# logmega082.net
KiCad netlist of a schematic drawn in EAGLE
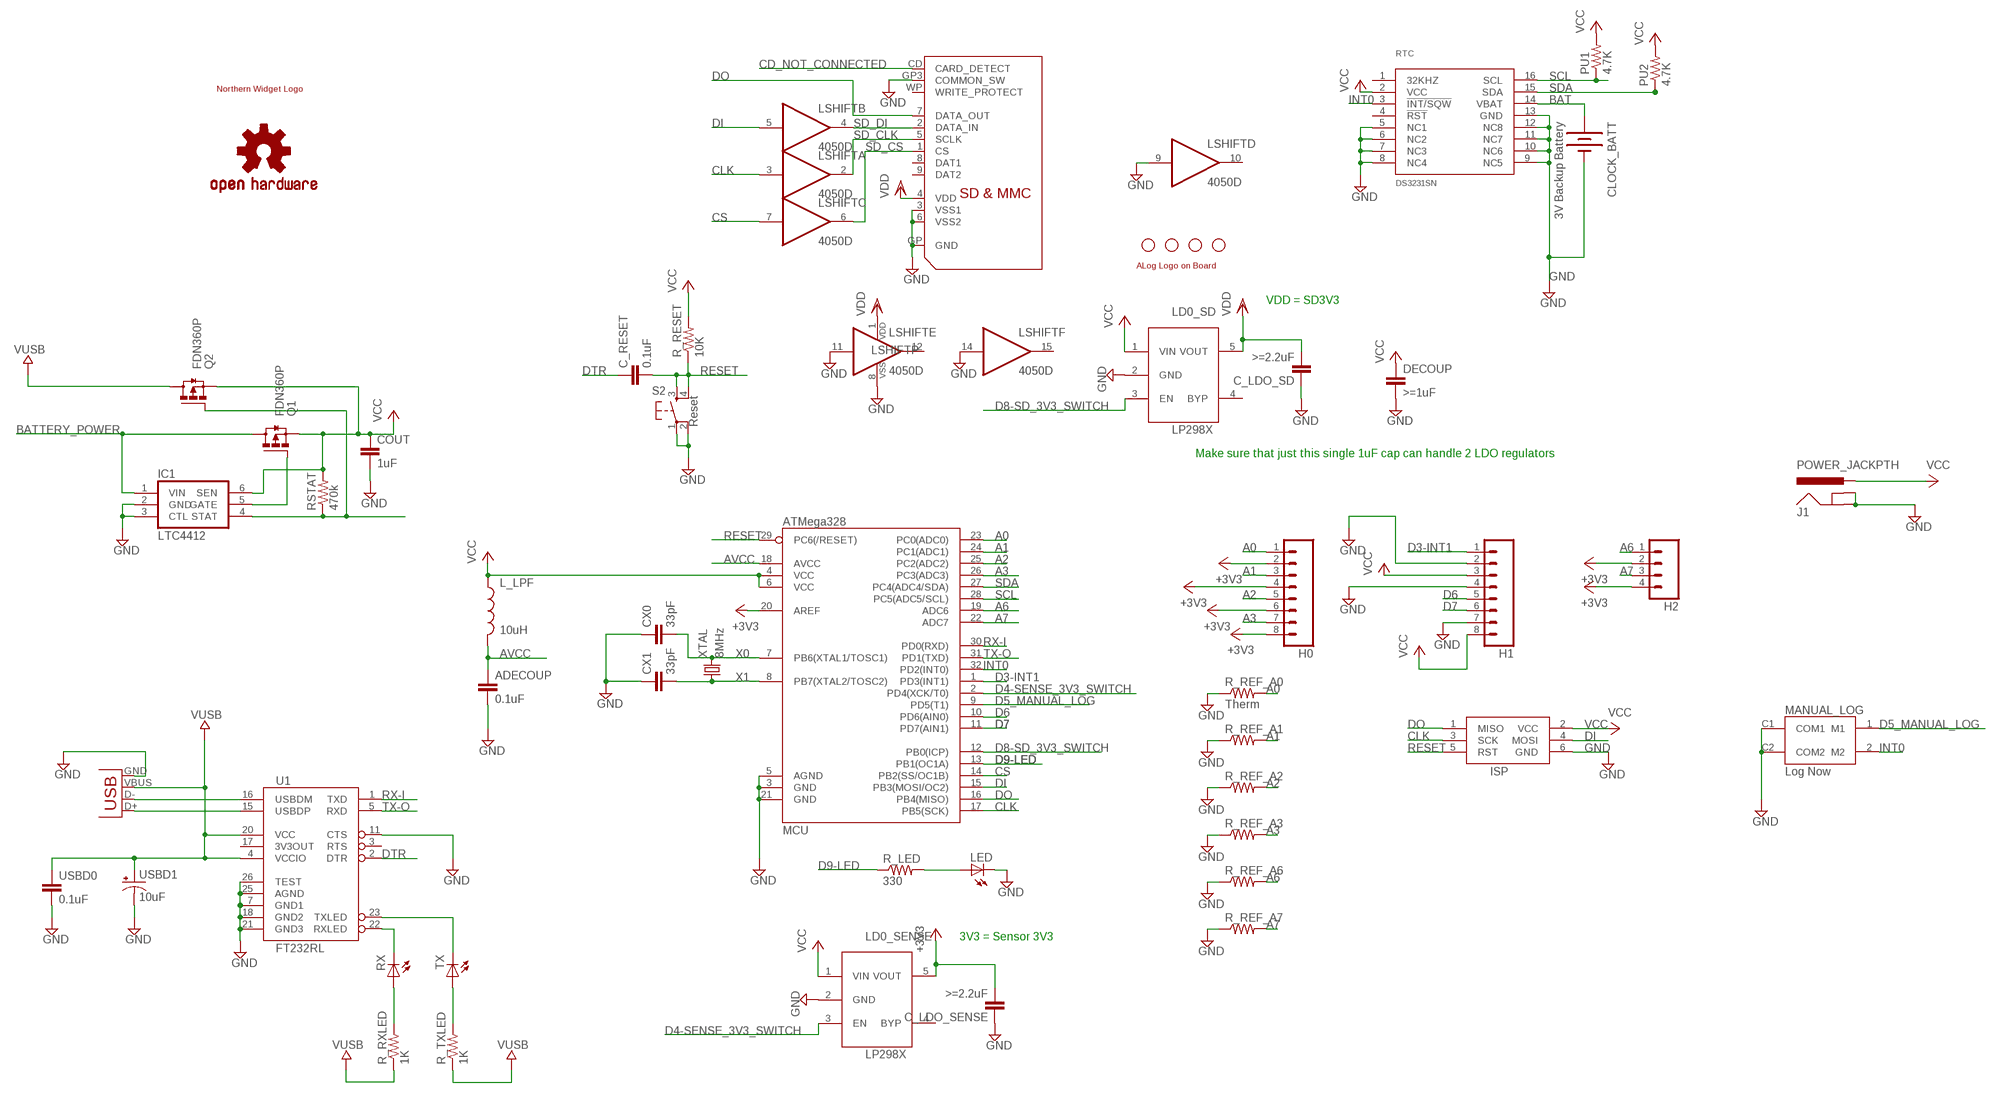
[diagram p0: schematic, sheet 1, part 1 of 2]
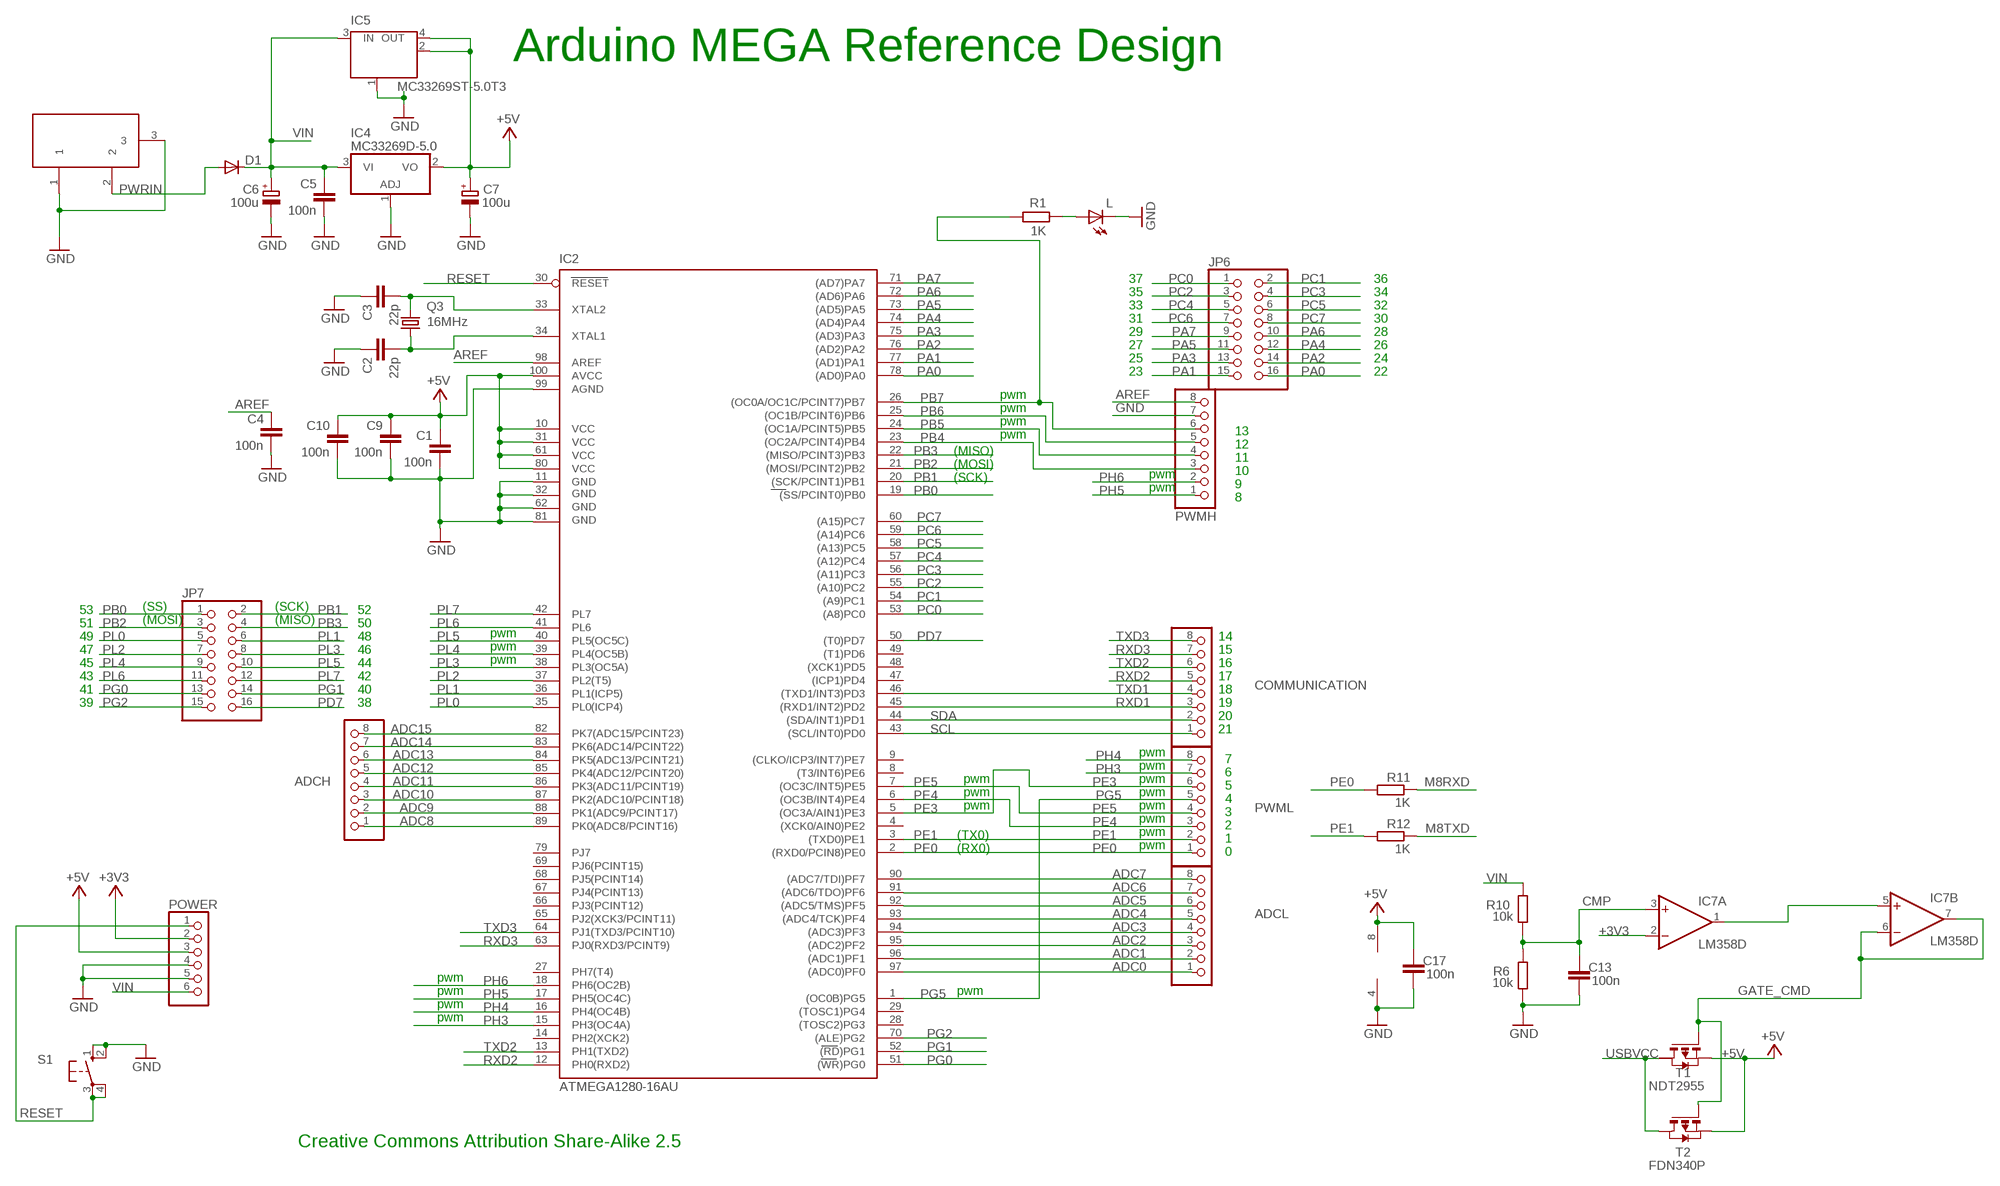
[diagram p1: schematic, sheet 1, part 2 of 2]

(export (version "E")
  (design (tool "Eeschema 10.0.6"))
  (components
    (comp (ref "ADCH")
      (value "PINHD-1X8")
      (footprint "eagle-import:1X08")
      (libsource (lib "eagle-import") (part "PINHD-1X8"))
    )
    (comp (ref "ADCL")
      (value "PINHD-1X8")
      (footprint "eagle-import:1X08")
      (libsource (lib "eagle-import") (part "PINHD-1X8"))
    )
    (comp (ref "ADECOUP")
      (value "0.1uF")
      (footprint "eagle-import:C0603")
      (libsource (lib "eagle-import") (part "resistor_C-EUC0603"))
    )
    (comp (ref "C1")
      (value "100n")
      (footprint "eagle-import:C0805RND")
      (libsource (lib "eagle-import") (part "rcl_C-EU"))
    )
    (comp (ref "C2")
      (value "22p")
      (footprint "eagle-import:C0805RND")
      (libsource (lib "eagle-import") (part "rcl_C-EU"))
    )
    (comp (ref "C3")
      (value "22p")
      (footprint "eagle-import:C0805RND")
      (libsource (lib "eagle-import") (part "rcl_C-EU"))
    )
    (comp (ref "C4")
      (value "100n")
      (footprint "eagle-import:C0805RND")
      (libsource (lib "eagle-import") (part "rcl_C-EU"))
    )
    (comp (ref "C5")
      (value "100n")
      (footprint "eagle-import:C0805RND")
      (libsource (lib "eagle-import") (part "rcl_C-EU"))
    )
    (comp (ref "C6")
      (value "100u")
      (footprint "eagle-import:SMC_D")
      (libsource (lib "eagle-import") (part "CPOL-EUSMCD"))
    )
    (comp (ref "C7")
      (value "100u")
      (footprint "eagle-import:SMC_D")
      (libsource (lib "eagle-import") (part "CPOL-EUSMCD"))
    )
    (comp (ref "C9")
      (value "100n")
      (footprint "eagle-import:C0805RND")
      (libsource (lib "eagle-import") (part "rcl_C-EU"))
    )
    (comp (ref "C10")
      (value "100n")
      (footprint "eagle-import:C0805RND")
      (libsource (lib "eagle-import") (part "rcl_C-EU"))
    )
    (comp (ref "C13")
      (value "100n")
      (footprint "eagle-import:C0805RND")
      (libsource (lib "eagle-import") (part "rcl_C-EU"))
    )
    (comp (ref "C17")
      (value "100n")
      (footprint "eagle-import:C0805RND")
      (libsource (lib "eagle-import") (part "rcl_C-EU"))
    )
    (comp (ref "CLOCK_BATT")
      (value "3V Backup Battery")
      (footprint "eagle-import:BATTCON_12MM_PTH")
      (libsource (lib "eagle-import") (part "BATTERY12PTH"))
    )
    (comp (ref "COMMUNICATION")
      (value "PINHD-1X8")
      (footprint "eagle-import:1X08")
      (libsource (lib "eagle-import") (part "PINHD-1X8"))
    )
    (comp (ref "COUT")
      (value "1uF")
      (footprint "eagle-import:C0603-ROUND")
      (libsource (lib "eagle-import") (part "C-EUC0603"))
    )
    (comp (ref "CX0")
      (value "33pF")
      (footprint "eagle-import:C0603")
      (libsource (lib "eagle-import") (part "resistor_C-EUC0603"))
    )
    (comp (ref "CX1")
      (value "33pF")
      (footprint "eagle-import:C0603")
      (libsource (lib "eagle-import") (part "resistor_C-EUC0603"))
    )
    (comp (ref "C_LDO_SD")
      (value ">=2.2uF")
      (footprint "eagle-import:C0603")
      (libsource (lib "eagle-import") (part "resistor_C-EUC0603"))
    )
    (comp (ref "C_LDO_SENSE")
      (value ">=2.2uF")
      (footprint "eagle-import:C0603")
      (libsource (lib "eagle-import") (part "resistor_C-EUC0603"))
    )
    (comp (ref "C_RESET")
      (value "0.1uF")
      (footprint "eagle-import:C0603")
      (libsource (lib "eagle-import") (part "resistor_C-EUC0603"))
    )
    (comp (ref "D1")
      (value "DIODE-SMB")
      (footprint "eagle-import:SMB")
      (libsource (lib "eagle-import") (part "DIODE-SMB"))
    )
    (comp (ref "DECOUP")
      (value ">=1uF")
      (footprint "eagle-import:C0603")
      (libsource (lib "eagle-import") (part "resistor_C-EUC0603"))
    )
    (comp (ref "H0")
      (value "M083.5MM-8")
      (footprint "eagle-import:SCREWTERMINAL-3.5MM-8")
      (libsource (lib "eagle-import") (part "M083.5MM-8"))
    )
    (comp (ref "H1")
      (value "M083.5MM-8")
      (footprint "eagle-import:SCREWTERMINAL-3.5MM-8")
      (libsource (lib "eagle-import") (part "M083.5MM-8"))
    )
    (comp (ref "H2")
      (value "M04SCREW")
      (footprint "eagle-import:SCREWTERMINAL-3.5MM-4")
      (libsource (lib "eagle-import") (part "M04SCREW"))
    )
    (comp (ref "IC1")
      (value "LTC4412")
      (footprint "eagle-import:TSOT23-6")
      (libsource (lib "eagle-import") (part "LTC4412S6E"))
    )
    (comp (ref "IC2")
      (value "ATMEGA1280-16AU")
      (footprint "eagle-import:TQFP100")
      (libsource (lib "eagle-import") (part "ATMEGAAU1280-16"))
    )
    (comp (ref "IC4")
      (value "MC33269D-5.0")
      (footprint "eagle-import:DPACK")
      (libsource (lib "eagle-import") (part "MC33269?D-5.0"))
    )
    (comp (ref "IC5")
      (value "MC33269ST-5.0T3")
      (footprint "eagle-import:SOT223")
      (libsource (lib "eagle-import") (part "MC33269ST-3.3T3"))
    )
    (comp (ref "IC7")
      (value "LM358D")
      (footprint "eagle-import:SO08")
      (libsource (lib "eagle-import") (part "LM358D"))
    )
    (comp (ref "ISP")
      (value "AVRISP-6")
      (footprint "eagle-import:AVRISP")
      (libsource (lib "eagle-import") (part "AVRISP-6"))
    )
    (comp (ref "J1")
      (value "POWER_JACKPTH")
      (footprint "eagle-import:POWER_JACK_PTH")
      (libsource (lib "eagle-import") (part "POWER_JACKPTH"))
    )
    (comp (ref "JP1")
      (value "STAND-OFF")
      (footprint "eagle-import:STAND-OFF")
      (libsource (lib "eagle-import") (part "STAND-OFF"))
    )
    (comp (ref "JP2")
      (value "STAND-OFF")
      (footprint "eagle-import:STAND-OFF")
      (libsource (lib "eagle-import") (part "STAND-OFF"))
    )
    (comp (ref "JP3")
      (value "STAND-OFF")
      (footprint "eagle-import:STAND-OFF")
      (libsource (lib "eagle-import") (part "STAND-OFF"))
    )
    (comp (ref "JP4")
      (value "STAND-OFF")
      (footprint "eagle-import:STAND-OFF")
      (libsource (lib "eagle-import") (part "STAND-OFF"))
    )
    (comp (ref "JP5")
      (value "USB-B")
      (footprint "eagle-import:USB-B-PTH")
      (libsource (lib "eagle-import") (part "USBPTH"))
    )
    (comp (ref "JP6")
      (value "PINHD-2X8")
      (footprint "eagle-import:2X08")
      (libsource (lib "eagle-import") (part "PINHD-2X8"))
    )
    (comp (ref "JP7")
      (value "PINHD-2X8")
      (footprint "eagle-import:2X08")
      (libsource (lib "eagle-import") (part "PINHD-2X8"))
    )
    (comp (ref "L")
      (value "LED0805ROUND")
      (footprint "eagle-import:0805RND")
      (libsource (lib "eagle-import") (part "LED0805ROUND"))
    )
    (comp (ref "LD0_SD")
      (value "LP2985")
      (footprint "eagle-import:SOT23-5L")
      (libsource (lib "eagle-import") (part "LP298XS"))
    )
    (comp (ref "LD0_SENSE")
      (value "LP2985")
      (footprint "eagle-import:SOT23-5L")
      (libsource (lib "eagle-import") (part "LP298XS"))
    )
    (comp (ref "LED")
      (value "LED3MM")
      (footprint "eagle-import:LED3MM")
      (libsource (lib "eagle-import") (part "LED3MM"))
    )
    (comp (ref "LOGO1")
      (value "OSHW-LOGOM")
      (footprint "eagle-import:OSHW-LOGO-M")
      (libsource (lib "eagle-import") (part "OSHW-LOGOM"))
    )
    (comp (ref "LSHIFT")
      (value "4050D")
      (footprint "eagle-import:SO16")
      (libsource (lib "eagle-import") (part "4050D"))
    )
    (comp (ref "L_LPF")
      (value "10uH")
      (footprint "eagle-import:0805")
      (libsource (lib "eagle-import") (part "INDUCTOR0805"))
    )
    (comp (ref "MANUAL_LOG")
      (value "Log Now")
      (footprint "eagle-import:TL_BUTTON")
      (libsource (lib "eagle-import") (part "TL3350'TL3350'"))
    )
    (comp (ref "MCU")
      (value "ATMega328")
      (footprint "eagle-import:TQFP32-08")
      (libsource (lib "eagle-import") (part "ATMEGA168"))
    )
    (comp (ref "POWER")
      (value "PINHD-1X6")
      (footprint "eagle-import:1X06")
      (libsource (lib "eagle-import") (part "PINHD-1X6"))
    )
    (comp (ref "PU1")
      (value "4.7K")
      (footprint "eagle-import:R0603@1")
      (libsource (lib "eagle-import") (part "R-US_R0603"))
    )
    (comp (ref "PU2")
      (value "4.7K")
      (footprint "eagle-import:R0603@1")
      (libsource (lib "eagle-import") (part "R-US_R0603"))
    )
    (comp (ref "PWMH")
      (value "PINHD-1X8")
      (footprint "eagle-import:1X08")
      (libsource (lib "eagle-import") (part "PINHD-1X8"))
    )
    (comp (ref "PWML")
      (value "PINHD-1X8")
      (footprint "eagle-import:1X08")
      (libsource (lib "eagle-import") (part "PINHD-1X8"))
    )
    (comp (ref "Q1")
      (value "FDN360P")
      (footprint "eagle-import:SUPER-SOT3")
      (libsource (lib "eagle-import") (part "FDN360P"))
    )
    (comp (ref "Q2")
      (value "FDN360P")
      (footprint "eagle-import:SUPER-SOT3")
      (libsource (lib "eagle-import") (part "FDN360P"))
    )
    (comp (ref "Q3")
      (value "16MHz")
      (footprint "eagle-import:HC49_S")
      (libsource (lib "eagle-import") (part "CRYTALHC49S"))
    )
    (comp (ref "R1")
      (value "1K")
      (footprint "eagle-import:R0805RND")
      (libsource (lib "eagle-import") (part "rcl_R-EU_"))
    )
    (comp (ref "R6")
      (value "10k")
      (footprint "eagle-import:R0805RND")
      (libsource (lib "eagle-import") (part "rcl_R-EU_"))
    )
    (comp (ref "R10")
      (value "10k")
      (footprint "eagle-import:R0805RND")
      (libsource (lib "eagle-import") (part "rcl_R-EU_"))
    )
    (comp (ref "R11")
      (value "1K")
      (footprint "eagle-import:RCL_0805RND")
      (libsource (lib "eagle-import") (part "R-EU_"))
    )
    (comp (ref "R12")
      (value "1K")
      (footprint "eagle-import:RCL_0805RND")
      (libsource (lib "eagle-import") (part "R-EU_"))
    )
    (comp (ref "RSTAT")
      (value "470k")
      (footprint "eagle-import:R0603@1")
      (libsource (lib "eagle-import") (part "R-US_R0603"))
    )
    (comp (ref "RTC")
      (value "DS3231SN")
      (footprint "eagle-import:SO16W")
      (libsource (lib "eagle-import") (part "DS3231SN"))
    )
    (comp (ref "RX")
      (value "LED0603")
      (footprint "eagle-import:LED-0603")
      (libsource (lib "eagle-import") (part "SparkFun-LED_LED0603"))
    )
    (comp (ref "R_LED")
      (value "330")
      (footprint "eagle-import:R0603@1")
      (libsource (lib "eagle-import") (part "R-US_R0603"))
    )
    (comp (ref "R_REF_A0")
      (value "Therm")
      (footprint "eagle-import:0207_10")
      (libsource (lib "eagle-import") (part "resistor_R-US_0207/10"))
    )
    (comp (ref "R_REF_A1")
      (value "R-US_0207/10")
      (footprint "eagle-import:0207_10")
      (libsource (lib "eagle-import") (part "resistor_R-US_0207/10"))
    )
    (comp (ref "R_REF_A2")
      (value "R-US_0207/10")
      (footprint "eagle-import:0207_10")
      (libsource (lib "eagle-import") (part "resistor_R-US_0207/10"))
    )
    (comp (ref "R_REF_A3")
      (value "R-US_0207/10")
      (footprint "eagle-import:0207_10")
      (libsource (lib "eagle-import") (part "resistor_R-US_0207/10"))
    )
    (comp (ref "R_REF_A6")
      (value "R-US_0207/10")
      (footprint "eagle-import:0207_10")
      (libsource (lib "eagle-import") (part "resistor_R-US_0207/10"))
    )
    (comp (ref "R_REF_A7")
      (value "R-US_0207/10")
      (footprint "eagle-import:0207_10")
      (libsource (lib "eagle-import") (part "resistor_R-US_0207/10"))
    )
    (comp (ref "R_RESET")
      (value "10K")
      (footprint "eagle-import:R0603@1")
      (libsource (lib "eagle-import") (part "R-US_R0603"))
    )
    (comp (ref "R_RXLED")
      (value "1K")
      (footprint "eagle-import:R0603@1")
      (libsource (lib "eagle-import") (part "R-US_R0603"))
    )
    (comp (ref "R_TXLED")
      (value "1K")
      (footprint "eagle-import:R0603@1")
      (libsource (lib "eagle-import") (part "R-US_R0603"))
    )
    (comp (ref "S1")
      (value "10-XX")
      (footprint "eagle-import:B3F-10XX")
      (libsource (lib "eagle-import") (part "10-XX"))
    )
    (comp (ref "S2")
      (value "Reset")
      (footprint "eagle-import:TACTILE_SWITCH_SMD")
      (libsource (lib "eagle-import") (part "TAC_SWITCHSND"))
    )
    (comp (ref "SD")
      (value "SDMMC06132")
      (footprint "eagle-import:06132")
      (libsource (lib "eagle-import") (part "SDMMC06132"))
    )
    (comp (ref "T1")
      (value "NDT2955")
      (footprint "eagle-import:SOT223")
      (libsource (lib "eagle-import") (part "PMOSSOT223"))
    )
    (comp (ref "T2")
      (value "FDN340P")
      (footprint "eagle-import:SOT-23")
      (libsource (lib "eagle-import") (part "PMOSSOT23"))
    )
    (comp (ref "TX")
      (value "LED0603")
      (footprint "eagle-import:LED-0603")
      (libsource (lib "eagle-import") (part "SparkFun-LED_LED0603"))
    )
    (comp (ref "U$1")
      (value "NWLOGO")
      (footprint "eagle-import:NWLOGO")
      (libsource (lib "eagle-import") (part "NWLOGO"))
    )
    (comp (ref "U$2")
      (value "ALOG_LOGO_V1_5.5MM")
      (footprint "eagle-import:ALOG_LOGO_V1_SMALL")
      (libsource (lib "eagle-import") (part "ALOG_LOGO_V1_5.5MM"))
    )
    (comp (ref "U1")
      (value "FT232RL")
      (footprint "eagle-import:SSOP28DB")
      (libsource (lib "eagle-import") (part "FT232RL-BASICSSOP"))
    )
    (comp (ref "USBD0")
      (value "0.1uF")
      (footprint "eagle-import:C0603")
      (libsource (lib "eagle-import") (part "resistor_C-EUC0603"))
    )
    (comp (ref "USBD1")
      (value "10uF")
      (footprint "eagle-import:EIA3216")
      (libsource (lib "eagle-import") (part "CAP_POL1206"))
    )
    (comp (ref "X2")
      (value "DC21MMX")
      (footprint "eagle-import:DC-21MM")
      (libsource (lib "eagle-import") (part "DC21MMX"))
    )
    (comp (ref "XTAL")
      (value "8MHz")
      (footprint "eagle-import:HC49U-V")
      (libsource (lib "eagle-import") (part "CRYSTALHC49UV"))
    )
  )
  (nets
    (net (code "1") (name "+3V3") (class "Default")
      (node (ref "C_LDO_SENSE") (pin "2") (pinfunction "2_2") (pintype "passive"))
      (node (ref "H0") (pin "2") (pinfunction "2_2") (pintype "passive"))
      (node (ref "H0") (pin "4") (pinfunction "4_4") (pintype "passive"))
      (node (ref "H0") (pin "6") (pinfunction "6_6") (pintype "passive"))
      (node (ref "H0") (pin "8") (pinfunction "8_8") (pintype "passive"))
      (node (ref "H2") (pin "2") (pinfunction "2_2") (pintype "passive"))
      (node (ref "H2") (pin "4") (pinfunction "4_4") (pintype "passive"))
      (node (ref "IC7") (pin "2") (pinfunction "-IN_2") (pintype "input"))
      (node (ref "LD0_SENSE") (pin "5") (pinfunction "VOUT_5") (pintype "bidirectional"))
      (node (ref "MCU") (pin "20") (pinfunction "AREF_20") (pintype "bidirectional"))
      (node (ref "POWER") (pin "2") (pinfunction "2_2") (pintype "passive"))
    )
    (net (code "2") (name "+5V") (class "Default")
      (node (ref "C1") (pin "1") (pinfunction "1_1") (pintype "passive"))
      (node (ref "C10") (pin "1") (pinfunction "1_1") (pintype "passive"))
      (node (ref "C17") (pin "2") (pinfunction "2_2") (pintype "passive"))
      (node (ref "C7") (pin "+") (pinfunction "+_+") (pintype "passive"))
      (node (ref "C9") (pin "1") (pinfunction "1_1") (pintype "passive"))
      (node (ref "IC2") (pin "10") (pinfunction "VCC_10") (pintype "power_in"))
      (node (ref "IC2") (pin "100") (pinfunction "AVCC_100") (pintype "power_in"))
      (node (ref "IC2") (pin "31") (pinfunction "VCC1_31") (pintype "power_in"))
      (node (ref "IC2") (pin "61") (pinfunction "VCC2_61") (pintype "power_in"))
      (node (ref "IC2") (pin "80") (pinfunction "VCC3_80") (pintype "power_in"))
      (node (ref "IC4") (pin "2") (pinfunction "VO_2") (pintype "passive"))
      (node (ref "IC5") (pin "2") (pinfunction "OUT_2") (pintype "passive"))
      (node (ref "IC5") (pin "4") (pinfunction "OUT_4") (pintype "passive"))
      (node (ref "IC7") (pin "8") (pinfunction "V+_8") (pintype "power_in"))
      (node (ref "POWER") (pin "3") (pinfunction "3_3") (pintype "passive"))
      (node (ref "T1") (pin "3") (pinfunction "S_3") (pintype "passive"))
      (node (ref "T2") (pin "2") (pinfunction "S_2") (pintype "passive"))
    )
    (net (code "3") (name "/A0") (class "Default")
      (node (ref "H0") (pin "1") (pinfunction "1_1") (pintype "passive"))
      (node (ref "MCU") (pin "23") (pinfunction "PC0(ADC0)_23") (pintype "bidirectional"))
      (node (ref "R_REF_A0") (pin "2") (pinfunction "2_2") (pintype "passive"))
    )
    (net (code "4") (name "/A1") (class "Default")
      (node (ref "H0") (pin "3") (pinfunction "3_3") (pintype "passive"))
      (node (ref "MCU") (pin "24") (pinfunction "PC1(ADC1)_24") (pintype "bidirectional"))
      (node (ref "R_REF_A1") (pin "2") (pinfunction "2_2") (pintype "passive"))
    )
    (net (code "5") (name "/A2") (class "Default")
      (node (ref "H0") (pin "5") (pinfunction "5_5") (pintype "passive"))
      (node (ref "MCU") (pin "25") (pinfunction "PC2(ADC2)_25") (pintype "bidirectional"))
      (node (ref "R_REF_A2") (pin "2") (pinfunction "2_2") (pintype "passive"))
    )
    (net (code "6") (name "/A3") (class "Default")
      (node (ref "H0") (pin "7") (pinfunction "7_7") (pintype "passive"))
      (node (ref "MCU") (pin "26") (pinfunction "PC3(ADC3)_26") (pintype "bidirectional"))
      (node (ref "R_REF_A3") (pin "2") (pinfunction "2_2") (pintype "passive"))
    )
    (net (code "7") (name "/A6") (class "Default")
      (node (ref "H2") (pin "1") (pinfunction "1_1") (pintype "passive"))
      (node (ref "MCU") (pin "19") (pinfunction "ADC6_19") (pintype "bidirectional"))
      (node (ref "R_REF_A6") (pin "2") (pinfunction "2_2") (pintype "passive"))
    )
    (net (code "8") (name "/A7") (class "Default")
      (node (ref "H2") (pin "3") (pinfunction "3_3") (pintype "passive"))
      (node (ref "MCU") (pin "22") (pinfunction "ADC7_22") (pintype "bidirectional"))
      (node (ref "R_REF_A7") (pin "2") (pinfunction "2_2") (pintype "passive"))
    )
    (net (code "9") (name "/ADC0") (class "Default")
      (node (ref "ADCL") (pin "1") (pinfunction "1_1") (pintype "passive"))
      (node (ref "IC2") (pin "97") (pinfunction "(ADC0)PF0_97") (pintype "bidirectional"))
    )
    (net (code "10") (name "/ADC1") (class "Default")
      (node (ref "ADCL") (pin "2") (pinfunction "2_2") (pintype "passive"))
      (node (ref "IC2") (pin "96") (pinfunction "(ADC1)PF1_96") (pintype "bidirectional"))
    )
    (net (code "11") (name "/ADC2") (class "Default")
      (node (ref "ADCL") (pin "3") (pinfunction "3_3") (pintype "passive"))
      (node (ref "IC2") (pin "95") (pinfunction "(ADC2)PF2_95") (pintype "bidirectional"))
    )
    (net (code "12") (name "/ADC3") (class "Default")
      (node (ref "ADCL") (pin "4") (pinfunction "4_4") (pintype "passive"))
      (node (ref "IC2") (pin "94") (pinfunction "(ADC3)PF3_94") (pintype "bidirectional"))
    )
    (net (code "13") (name "/ADC4") (class "Default")
      (node (ref "ADCL") (pin "5") (pinfunction "5_5") (pintype "passive"))
      (node (ref "IC2") (pin "93") (pinfunction "(ADC4/TCK)PF4_93") (pintype "bidirectional"))
    )
    (net (code "14") (name "/ADC5") (class "Default")
      (node (ref "ADCL") (pin "6") (pinfunction "6_6") (pintype "passive"))
      (node (ref "IC2") (pin "92") (pinfunction "(ADC5/TMS)PF5_92") (pintype "bidirectional"))
    )
    (net (code "15") (name "/ADC6") (class "Default")
      (node (ref "ADCL") (pin "7") (pinfunction "7_7") (pintype "passive"))
      (node (ref "IC2") (pin "91") (pinfunction "(ADC6/TDO)PF6_91") (pintype "bidirectional"))
    )
    (net (code "16") (name "/ADC7") (class "Default")
      (node (ref "ADCL") (pin "8") (pinfunction "8_8") (pintype "passive"))
      (node (ref "IC2") (pin "90") (pinfunction "(ADC7/TDI)PF7_90") (pintype "bidirectional"))
    )
    (net (code "17") (name "/ADC8") (class "Default")
      (node (ref "ADCH") (pin "1") (pinfunction "1_1") (pintype "passive"))
      (node (ref "IC2") (pin "89") (pinfunction "PK0(ADC8/PCINT16)_89") (pintype "bidirectional"))
    )
    (net (code "18") (name "/ADC9") (class "Default")
      (node (ref "ADCH") (pin "2") (pinfunction "2_2") (pintype "passive"))
      (node (ref "IC2") (pin "88") (pinfunction "PK1(ADC9/PCINT17)_88") (pintype "bidirectional"))
    )
    (net (code "19") (name "/ADC10") (class "Default")
      (node (ref "ADCH") (pin "3") (pinfunction "3_3") (pintype "passive"))
      (node (ref "IC2") (pin "87") (pinfunction "PK2(ADC10/PCINT18)_87") (pintype "bidirectional"))
    )
    (net (code "20") (name "/ADC11") (class "Default")
      (node (ref "ADCH") (pin "4") (pinfunction "4_4") (pintype "passive"))
      (node (ref "IC2") (pin "86") (pinfunction "PK3(ADC11/PCINT19)_86") (pintype "bidirectional"))
    )
    (net (code "21") (name "/ADC12") (class "Default")
      (node (ref "ADCH") (pin "5") (pinfunction "5_5") (pintype "passive"))
      (node (ref "IC2") (pin "85") (pinfunction "PK4(ADC12/PCINT20)_85") (pintype "bidirectional"))
    )
    (net (code "22") (name "/ADC13") (class "Default")
      (node (ref "ADCH") (pin "6") (pinfunction "6_6") (pintype "passive"))
      (node (ref "IC2") (pin "84") (pinfunction "PK5(ADC13/PCINT21)_84") (pintype "bidirectional"))
    )
    (net (code "23") (name "/ADC14") (class "Default")
      (node (ref "ADCH") (pin "7") (pinfunction "7_7") (pintype "passive"))
      (node (ref "IC2") (pin "83") (pinfunction "PK6(ADC14/PCINT22)_83") (pintype "bidirectional"))
    )
    (net (code "24") (name "/ADC15") (class "Default")
      (node (ref "ADCH") (pin "8") (pinfunction "8_8") (pintype "passive"))
      (node (ref "IC2") (pin "82") (pinfunction "PK7(ADC15/PCINT23)_82") (pintype "bidirectional"))
    )
    (net (code "25") (name "/AREF") (class "Default")
      (node (ref "C4") (pin "1") (pinfunction "1_1") (pintype "passive"))
      (node (ref "IC2") (pin "98") (pinfunction "AREF_98") (pintype "bidirectional"))
      (node (ref "PWMH") (pin "8") (pinfunction "8_8") (pintype "passive"))
    )
    (net (code "26") (name "/AVCC") (class "Default")
      (node (ref "ADECOUP") (pin "1") (pinfunction "1_1") (pintype "passive"))
      (node (ref "L_LPF") (pin "2") (pinfunction "2_2") (pintype "passive"))
      (node (ref "MCU") (pin "18") (pinfunction "AVCC_18") (pintype "bidirectional"))
    )
    (net (code "27") (name "/BAT") (class "Default")
      (node (ref "CLOCK_BATT") (pin "VCC@1") (pinfunction "+_VCC@1") (pintype "power_in"))
      (node (ref "RTC") (pin "14") (pinfunction "VBAT_14") (pintype "bidirectional"))
    )
    (net (code "28") (name "/BATTERY_POWER") (class "Default")
      (node (ref "IC1") (pin "1") (pinfunction "VIN_1") (pintype "input"))
      (node (ref "Q1") (pin "3") (pinfunction "D_3") (pintype "passive"))
    )
    (net (code "29") (name "/CD_NOT_CONNECTED") (class "Default")
      (node (ref "SD") (pin "CD") (pinfunction "CARD_DETECT_CD") (pintype "passive"))
    )
    (net (code "30") (name "/CLK") (class "Default")
      (node (ref "ISP") (pin "3") (pinfunction "SCK_3") (pintype "output"))
      (node (ref "LSHIFT") (pin "3") (pinfunction "I_3") (pintype "input"))
      (node (ref "MCU") (pin "17") (pinfunction "PB5(SCK)_17") (pintype "bidirectional"))
    )
    (net (code "31") (name "/CMP") (class "Default")
      (node (ref "C13") (pin "2") (pinfunction "2_2") (pintype "passive"))
      (node (ref "IC7") (pin "3") (pinfunction "+IN_3") (pintype "input"))
      (node (ref "R10") (pin "1") (pinfunction "1_1") (pintype "passive"))
      (node (ref "R6") (pin "2") (pinfunction "2_2") (pintype "passive"))
    )
    (net (code "32") (name "/CS") (class "Default")
      (node (ref "LSHIFT") (pin "7") (pinfunction "I_7") (pintype "input"))
      (node (ref "MCU") (pin "14") (pinfunction "PB2(SS/OC1B)_14") (pintype "bidirectional"))
    )
    (net (code "33") (name "/D3-INT1") (class "Default")
      (node (ref "H1") (pin "1") (pinfunction "1_1") (pintype "passive"))
      (node (ref "MCU") (pin "1") (pinfunction "PD3(INT1)_1") (pintype "bidirectional"))
    )
    (net (code "34") (name "/D4-SENSE_3V3_SWITCH") (class "Default")
      (node (ref "LD0_SENSE") (pin "3") (pinfunction "EN_3") (pintype "bidirectional"))
      (node (ref "MCU") (pin "2") (pinfunction "PD4(XCK/T0)_2") (pintype "bidirectional"))
    )
    (net (code "35") (name "/D5_MANUAL_LOG") (class "Default")
      (node (ref "MANUAL_LOG") (pin "1") (pinfunction "M1_1") (pintype "bidirectional"))
      (node (ref "MCU") (pin "9") (pinfunction "PD5(T1)_9") (pintype "bidirectional"))
    )
    (net (code "36") (name "/D6") (class "Default")
      (node (ref "H1") (pin "5") (pinfunction "5_5") (pintype "passive"))
      (node (ref "MCU") (pin "10") (pinfunction "PD6(AIN0)_10") (pintype "bidirectional"))
    )
    (net (code "37") (name "/D7") (class "Default")
      (node (ref "H1") (pin "6") (pinfunction "6_6") (pintype "passive"))
      (node (ref "MCU") (pin "11") (pinfunction "PD7(AIN1)_11") (pintype "bidirectional"))
    )
    (net (code "38") (name "/D8-SD_3V3_SWITCH") (class "Default")
      (node (ref "LD0_SD") (pin "3") (pinfunction "EN_3") (pintype "bidirectional"))
      (node (ref "MCU") (pin "12") (pinfunction "PB0(ICP)_12") (pintype "bidirectional"))
    )
    (net (code "39") (name "/D9-LED") (class "Default")
      (node (ref "MCU") (pin "13") (pinfunction "PB1(OC1A)_13") (pintype "bidirectional"))
      (node (ref "R_LED") (pin "1") (pinfunction "1_1") (pintype "passive"))
    )
    (net (code "40") (name "/DI") (class "Default")
      (node (ref "ISP") (pin "4") (pinfunction "MOSI_4") (pintype "output"))
      (node (ref "LSHIFT") (pin "5") (pinfunction "I_5") (pintype "input"))
      (node (ref "MCU") (pin "15") (pinfunction "PB3(MOSI/OC2)_15") (pintype "bidirectional"))
    )
    (net (code "41") (name "/DO") (class "Default")
      (node (ref "ISP") (pin "1") (pinfunction "MISO_1") (pintype "input"))
      (node (ref "MCU") (pin "16") (pinfunction "PB4(MISO)_16") (pintype "bidirectional"))
      (node (ref "SD") (pin "7") (pinfunction "DATA_OUT_7") (pintype "output"))
    )
    (net (code "42") (name "/DTR") (class "Default")
      (node (ref "C_RESET") (pin "1") (pinfunction "1_1") (pintype "passive"))
      (node (ref "U1") (pin "2") (pinfunction "DTR_2") (pintype "bidirectional"))
    )
    (net (code "43") (name "/GATE_CMD") (class "Default")
      (node (ref "IC7") (pin "6") (pinfunction "-IN_6") (pintype "input"))
      (node (ref "IC7") (pin "7") (pinfunction "OUT_7") (pintype "output"))
      (node (ref "T1") (pin "1") (pinfunction "G_1") (pintype "passive"))
      (node (ref "T2") (pin "3") (pinfunction "G_3") (pintype "passive"))
    )
    (net (code "44") (name "/INT0") (class "Default")
      (node (ref "MANUAL_LOG") (pin "2") (pinfunction "M2_2") (pintype "bidirectional"))
      (node (ref "MCU") (pin "32") (pinfunction "PD2(INT0)_32") (pintype "bidirectional"))
      (node (ref "RTC") (pin "3") (pinfunction "~{INT/SQW}_3") (pintype "bidirectional"))
    )
    (net (code "45") (name "/M8RXD") (class "Default")
      (node (ref "R11") (pin "P$1") (pinfunction "1_P$1") (pintype "passive"))
    )
    (net (code "46") (name "/M8TXD") (class "Default")
      (node (ref "R12") (pin "P$1") (pinfunction "1_P$1") (pintype "passive"))
    )
    (net (code "47") (name "/PA0") (class "Default")
      (node (ref "IC2") (pin "78") (pinfunction "(AD0)PA0_78") (pintype "bidirectional"))
      (node (ref "JP6") (pin "16") (pinfunction "16_16") (pintype "passive"))
    )
    (net (code "48") (name "/PA1") (class "Default")
      (node (ref "IC2") (pin "77") (pinfunction "(AD1)PA1_77") (pintype "bidirectional"))
      (node (ref "JP6") (pin "15") (pinfunction "15_15") (pintype "passive"))
    )
    (net (code "49") (name "/PA2") (class "Default")
      (node (ref "IC2") (pin "76") (pinfunction "(AD2)PA2_76") (pintype "bidirectional"))
      (node (ref "JP6") (pin "14") (pinfunction "14_14") (pintype "passive"))
    )
    (net (code "50") (name "/PA3") (class "Default")
      (node (ref "IC2") (pin "75") (pinfunction "(AD3)PA3_75") (pintype "bidirectional"))
      (node (ref "JP6") (pin "13") (pinfunction "13_13") (pintype "passive"))
    )
    (net (code "51") (name "/PA4") (class "Default")
      (node (ref "IC2") (pin "74") (pinfunction "(AD4)PA4_74") (pintype "bidirectional"))
      (node (ref "JP6") (pin "12") (pinfunction "12_12") (pintype "passive"))
    )
    (net (code "52") (name "/PA5") (class "Default")
      (node (ref "IC2") (pin "73") (pinfunction "(AD5)PA5_73") (pintype "bidirectional"))
      (node (ref "JP6") (pin "11") (pinfunction "11_11") (pintype "passive"))
    )
    (net (code "53") (name "/PA6") (class "Default")
      (node (ref "IC2") (pin "72") (pinfunction "(AD6)PA6_72") (pintype "bidirectional"))
      (node (ref "JP6") (pin "10") (pinfunction "10_10") (pintype "passive"))
    )
    (net (code "54") (name "/PA7") (class "Default")
      (node (ref "IC2") (pin "71") (pinfunction "(AD7)PA7_71") (pintype "bidirectional"))
      (node (ref "JP6") (pin "9") (pinfunction "9_9") (pintype "passive"))
    )
    (net (code "55") (name "/PB0") (class "Default")
      (node (ref "IC2") (pin "19") (pinfunction "(SS/PCINT0)PB0_19") (pintype "bidirectional"))
      (node (ref "JP7") (pin "1") (pinfunction "1_1") (pintype "passive"))
    )
    (net (code "56") (name "/PB1") (class "Default")
      (node (ref "IC2") (pin "20") (pinfunction "(SCK/PCINT1)PB1_20") (pintype "bidirectional"))
      (node (ref "JP7") (pin "2") (pinfunction "2_2") (pintype "passive"))
    )
    (net (code "57") (name "/PB2") (class "Default")
      (node (ref "IC2") (pin "21") (pinfunction "(MOSI/PCINT2)PB2_21") (pintype "bidirectional"))
      (node (ref "JP7") (pin "3") (pinfunction "3_3") (pintype "passive"))
    )
    (net (code "58") (name "/PB3") (class "Default")
      (node (ref "IC2") (pin "22") (pinfunction "(MISO/PCINT3)PB3_22") (pintype "bidirectional"))
      (node (ref "JP7") (pin "4") (pinfunction "4_4") (pintype "passive"))
    )
    (net (code "59") (name "/PB4") (class "Default")
      (node (ref "IC2") (pin "23") (pinfunction "(OC2A/PCINT4)PB4_23") (pintype "bidirectional"))
      (node (ref "PWMH") (pin "3") (pinfunction "3_3") (pintype "passive"))
    )
    (net (code "60") (name "/PB5") (class "Default")
      (node (ref "IC2") (pin "24") (pinfunction "(OC1A/PCINT5)PB5_24") (pintype "bidirectional"))
      (node (ref "PWMH") (pin "4") (pinfunction "4_4") (pintype "passive"))
    )
    (net (code "61") (name "/PB6") (class "Default")
      (node (ref "IC2") (pin "25") (pinfunction "(OC1B/PCINT6)PB6_25") (pintype "bidirectional"))
      (node (ref "PWMH") (pin "5") (pinfunction "5_5") (pintype "passive"))
    )
    (net (code "62") (name "/PB7") (class "Default")
      (node (ref "IC2") (pin "26") (pinfunction "(OC0A/OC1C/PCINT7)PB7_26") (pintype "bidirectional"))
      (node (ref "PWMH") (pin "6") (pinfunction "6_6") (pintype "passive"))
      (node (ref "R1") (pin "1") (pinfunction "1_1") (pintype "passive"))
    )
    (net (code "63") (name "/PC0") (class "Default")
      (node (ref "IC2") (pin "53") (pinfunction "(A8)PC0_53") (pintype "bidirectional"))
      (node (ref "JP6") (pin "1") (pinfunction "1_1") (pintype "passive"))
    )
    (net (code "64") (name "/PC1") (class "Default")
      (node (ref "IC2") (pin "54") (pinfunction "(A9)PC1_54") (pintype "bidirectional"))
      (node (ref "JP6") (pin "2") (pinfunction "2_2") (pintype "passive"))
    )
    (net (code "65") (name "/PC2") (class "Default")
      (node (ref "IC2") (pin "55") (pinfunction "(A10)PC2_55") (pintype "bidirectional"))
      (node (ref "JP6") (pin "3") (pinfunction "3_3") (pintype "passive"))
    )
    (net (code "66") (name "/PC3") (class "Default")
      (node (ref "IC2") (pin "56") (pinfunction "(A11)PC3_56") (pintype "bidirectional"))
      (node (ref "JP6") (pin "4") (pinfunction "4_4") (pintype "passive"))
    )
    (net (code "67") (name "/PC4") (class "Default")
      (node (ref "IC2") (pin "57") (pinfunction "(A12)PC4_57") (pintype "bidirectional"))
      (node (ref "JP6") (pin "5") (pinfunction "5_5") (pintype "passive"))
    )
    (net (code "68") (name "/PC5") (class "Default")
      (node (ref "IC2") (pin "58") (pinfunction "(A13)PC5_58") (pintype "bidirectional"))
      (node (ref "JP6") (pin "6") (pinfunction "6_6") (pintype "passive"))
    )
    (net (code "69") (name "/PC6") (class "Default")
      (node (ref "IC2") (pin "59") (pinfunction "(A14)PC6_59") (pintype "bidirectional"))
      (node (ref "JP6") (pin "7") (pinfunction "7_7") (pintype "passive"))
    )
    (net (code "70") (name "/PC7") (class "Default")
      (node (ref "IC2") (pin "60") (pinfunction "(A15)PC7_60") (pintype "bidirectional"))
      (node (ref "JP6") (pin "8") (pinfunction "8_8") (pintype "passive"))
    )
    (net (code "71") (name "/PD7") (class "Default")
      (node (ref "IC2") (pin "50") (pinfunction "(T0)PD7_50") (pintype "bidirectional"))
      (node (ref "JP7") (pin "16") (pinfunction "16_16") (pintype "passive"))
    )
    (net (code "72") (name "/PE0") (class "Default")
      (node (ref "IC2") (pin "2") (pinfunction "(RXD0/PCIN8)PE0_2") (pintype "bidirectional"))
      (node (ref "PWML") (pin "1") (pinfunction "1_1") (pintype "passive"))
      (node (ref "R11") (pin "P$2") (pinfunction "2_P$2") (pintype "passive"))
    )
    (net (code "73") (name "/PE1") (class "Default")
      (node (ref "IC2") (pin "3") (pinfunction "(TXD0)PE1_3") (pintype "bidirectional"))
      (node (ref "PWML") (pin "2") (pinfunction "2_2") (pintype "passive"))
      (node (ref "R12") (pin "P$2") (pinfunction "2_P$2") (pintype "passive"))
    )
    (net (code "74") (name "/PE3") (class "Default")
      (node (ref "IC2") (pin "5") (pinfunction "(OC3A/AIN1)PE3_5") (pintype "bidirectional"))
      (node (ref "PWML") (pin "6") (pinfunction "6_6") (pintype "passive"))
    )
    (net (code "75") (name "/PE4") (class "Default")
      (node (ref "IC2") (pin "6") (pinfunction "(OC3B/INT4)PE4_6") (pintype "bidirectional"))
      (node (ref "PWML") (pin "3") (pinfunction "3_3") (pintype "passive"))
    )
    (net (code "76") (name "/PE5") (class "Default")
      (node (ref "IC2") (pin "7") (pinfunction "(OC3C/INT5)PE5_7") (pintype "bidirectional"))
      (node (ref "PWML") (pin "4") (pinfunction "4_4") (pintype "passive"))
    )
    (net (code "77") (name "/PG0") (class "Default")
      (node (ref "IC2") (pin "51") (pinfunction "(WR)PG0_51") (pintype "bidirectional"))
      (node (ref "JP7") (pin "13") (pinfunction "13_13") (pintype "passive"))
    )
    (net (code "78") (name "/PG1") (class "Default")
      (node (ref "IC2") (pin "52") (pinfunction "(RD)PG1_52") (pintype "bidirectional"))
      (node (ref "JP7") (pin "14") (pinfunction "14_14") (pintype "passive"))
    )
    (net (code "79") (name "/PG2") (class "Default")
      (node (ref "IC2") (pin "70") (pinfunction "(ALE)PG2_70") (pintype "bidirectional"))
      (node (ref "JP7") (pin "15") (pinfunction "15_15") (pintype "passive"))
    )
    (net (code "80") (name "/PG5") (class "Default")
      (node (ref "IC2") (pin "1") (pinfunction "(OC0B)PG5_1") (pintype "bidirectional"))
      (node (ref "PWML") (pin "5") (pinfunction "5_5") (pintype "passive"))
    )
    (net (code "81") (name "/PH3") (class "Default")
      (node (ref "IC2") (pin "15") (pinfunction "PH3(OC4A)_15") (pintype "bidirectional"))
      (node (ref "PWML") (pin "7") (pinfunction "7_7") (pintype "passive"))
    )
    (net (code "82") (name "/PH4") (class "Default")
      (node (ref "IC2") (pin "16") (pinfunction "PH4(OC4B)_16") (pintype "bidirectional"))
      (node (ref "PWML") (pin "8") (pinfunction "8_8") (pintype "passive"))
    )
    (net (code "83") (name "/PH5") (class "Default")
      (node (ref "IC2") (pin "17") (pinfunction "PH5(OC4C)_17") (pintype "bidirectional"))
      (node (ref "PWMH") (pin "1") (pinfunction "1_1") (pintype "passive"))
    )
    (net (code "84") (name "/PH6") (class "Default")
      (node (ref "IC2") (pin "18") (pinfunction "PH6(OC2B)_18") (pintype "bidirectional"))
      (node (ref "PWMH") (pin "2") (pinfunction "2_2") (pintype "passive"))
    )
    (net (code "85") (name "/PL0") (class "Default")
      (node (ref "IC2") (pin "35") (pinfunction "PL0(ICP4)_35") (pintype "bidirectional"))
      (node (ref "JP7") (pin "5") (pinfunction "5_5") (pintype "passive"))
    )
    (net (code "86") (name "/PL1") (class "Default")
      (node (ref "IC2") (pin "36") (pinfunction "PL1(ICP5)_36") (pintype "bidirectional"))
      (node (ref "JP7") (pin "6") (pinfunction "6_6") (pintype "passive"))
    )
    (net (code "87") (name "/PL2") (class "Default")
      (node (ref "IC2") (pin "37") (pinfunction "PL2(T5)_37") (pintype "bidirectional"))
      (node (ref "JP7") (pin "7") (pinfunction "7_7") (pintype "passive"))
    )
    (net (code "88") (name "/PL3") (class "Default")
      (node (ref "IC2") (pin "38") (pinfunction "PL3(OC5A)_38") (pintype "bidirectional"))
      (node (ref "JP7") (pin "8") (pinfunction "8_8") (pintype "passive"))
    )
    (net (code "89") (name "/PL4") (class "Default")
      (node (ref "IC2") (pin "39") (pinfunction "PL4(OC5B)_39") (pintype "bidirectional"))
      (node (ref "JP7") (pin "9") (pinfunction "9_9") (pintype "passive"))
    )
    (net (code "90") (name "/PL5") (class "Default")
      (node (ref "IC2") (pin "40") (pinfunction "PL5(OC5C)_40") (pintype "bidirectional"))
      (node (ref "JP7") (pin "10") (pinfunction "10_10") (pintype "passive"))
    )
    (net (code "91") (name "/PL6") (class "Default")
      (node (ref "IC2") (pin "41") (pinfunction "PL6_41") (pintype "bidirectional"))
      (node (ref "JP7") (pin "11") (pinfunction "11_11") (pintype "passive"))
    )
    (net (code "92") (name "/PL7") (class "Default")
      (node (ref "IC2") (pin "42") (pinfunction "PL7_42") (pintype "bidirectional"))
      (node (ref "JP7") (pin "12") (pinfunction "12_12") (pintype "passive"))
    )
    (net (code "93") (name "/PWRIN") (class "Default")
      (node (ref "D1") (pin "A") (pinfunction "A_A") (pintype "passive"))
      (node (ref "X2") (pin "2") (pinfunction "2_2") (pintype "power_in"))
    )
    (net (code "94") (name "/RESET") (class "Default")
      (node (ref "C_RESET") (pin "2") (pinfunction "2_2") (pintype "passive"))
      (node (ref "IC2") (pin "30") (pinfunction "RESET_30") (pintype "input"))
      (node (ref "ISP") (pin "5") (pinfunction "RST_5") (pintype "output"))
      (node (ref "MCU") (pin "29") (pinfunction "PC6(/RESET)_29") (pintype "bidirectional"))
      (node (ref "POWER") (pin "1") (pinfunction "1_1") (pintype "passive"))
      (node (ref "R_RESET") (pin "1") (pinfunction "1_1") (pintype "passive"))
      (node (ref "S1") (pin "3") (pinfunction "P_3") (pintype "passive"))
      (node (ref "S1") (pin "4") (pinfunction "P1_4") (pintype "passive"))
      (node (ref "S2") (pin "3") (pinfunction "3_3") (pintype "passive"))
      (node (ref "S2") (pin "4") (pinfunction "4_4") (pintype "passive"))
    )
    (net (code "95") (name "/RX-I") (class "Default")
      (node (ref "MCU") (pin "30") (pinfunction "PD0(RXD)_30") (pintype "bidirectional"))
      (node (ref "U1") (pin "1") (pinfunction "TXD_1") (pintype "output"))
    )
    (net (code "96") (name "/RXD1") (class "Default")
      (node (ref "COMMUNICATION") (pin "3") (pinfunction "3_3") (pintype "passive"))
      (node (ref "IC2") (pin "45") (pinfunction "(RXD1/INT2)PD2_45") (pintype "bidirectional"))
    )
    (net (code "97") (name "/RXD2") (class "Default")
      (node (ref "COMMUNICATION") (pin "5") (pinfunction "5_5") (pintype "passive"))
      (node (ref "IC2") (pin "12") (pinfunction "PH0(RXD2)_12") (pintype "bidirectional"))
    )
    (net (code "98") (name "/RXD3") (class "Default")
      (node (ref "COMMUNICATION") (pin "7") (pinfunction "7_7") (pintype "passive"))
      (node (ref "IC2") (pin "63") (pinfunction "PJ0(RXD3/PCINT9)_63") (pintype "bidirectional"))
    )
    (net (code "99") (name "/SCL") (class "Default")
      (node (ref "COMMUNICATION") (pin "1") (pinfunction "1_1") (pintype "passive"))
      (node (ref "IC2") (pin "43") (pinfunction "(SCL/INT0)PD0_43") (pintype "bidirectional"))
      (node (ref "MCU") (pin "28") (pinfunction "PC5(ADC5/SCL)_28") (pintype "bidirectional"))
      (node (ref "PU1") (pin "1") (pinfunction "1_1") (pintype "passive"))
      (node (ref "RTC") (pin "16") (pinfunction "SCL_16") (pintype "bidirectional"))
    )
    (net (code "100") (name "/SDA") (class "Default")
      (node (ref "COMMUNICATION") (pin "2") (pinfunction "2_2") (pintype "passive"))
      (node (ref "IC2") (pin "44") (pinfunction "(SDA/INT1)PD1_44") (pintype "bidirectional"))
      (node (ref "MCU") (pin "27") (pinfunction "PC4(ADC4/SDA)_27") (pintype "bidirectional"))
      (node (ref "PU2") (pin "1") (pinfunction "1_1") (pintype "passive"))
      (node (ref "RTC") (pin "15") (pinfunction "SDA_15") (pintype "bidirectional"))
    )
    (net (code "101") (name "/SD_CLK") (class "Default")
      (node (ref "LSHIFT") (pin "2") (pinfunction "O_2") (pintype "output"))
      (node (ref "SD") (pin "5") (pinfunction "SCLK_5") (pintype "input"))
    )
    (net (code "102") (name "/SD_CS") (class "Default")
      (node (ref "LSHIFT") (pin "6") (pinfunction "O_6") (pintype "output"))
      (node (ref "SD") (pin "1") (pinfunction "CS_1") (pintype "input"))
    )
    (net (code "103") (name "/SD_DI") (class "Default")
      (node (ref "LSHIFT") (pin "4") (pinfunction "O_4") (pintype "output"))
      (node (ref "SD") (pin "2") (pinfunction "DATA_IN_2") (pintype "input"))
    )
    (net (code "104") (name "/TX-O") (class "Default")
      (node (ref "MCU") (pin "31") (pinfunction "PD1(TXD)_31") (pintype "bidirectional"))
      (node (ref "U1") (pin "5") (pinfunction "RXD_5") (pintype "input"))
    )
    (net (code "105") (name "/TXD1") (class "Default")
      (node (ref "COMMUNICATION") (pin "4") (pinfunction "4_4") (pintype "passive"))
      (node (ref "IC2") (pin "46") (pinfunction "(TXD1/INT3)PD3_46") (pintype "bidirectional"))
    )
    (net (code "106") (name "/TXD2") (class "Default")
      (node (ref "COMMUNICATION") (pin "6") (pinfunction "6_6") (pintype "passive"))
      (node (ref "IC2") (pin "13") (pinfunction "PH1(TXD2)_13") (pintype "bidirectional"))
    )
    (net (code "107") (name "/TXD3") (class "Default")
      (node (ref "COMMUNICATION") (pin "8") (pinfunction "8_8") (pintype "passive"))
      (node (ref "IC2") (pin "64") (pinfunction "PJ1(TXD3/PCINT10)_64") (pintype "bidirectional"))
    )
    (net (code "108") (name "/USBVCC") (class "Default")
      (node (ref "T1") (pin "2") (pinfunction "D_2") (pintype "passive"))
      (node (ref "T2") (pin "1") (pinfunction "D_1") (pintype "passive"))
    )
    (net (code "109") (name "/VIN") (class "Default")
      (node (ref "C5") (pin "1") (pinfunction "1_1") (pintype "passive"))
      (node (ref "C6") (pin "+") (pinfunction "+_+") (pintype "passive"))
      (node (ref "D1") (pin "C") (pinfunction "C_C") (pintype "passive"))
      (node (ref "IC4") (pin "3") (pinfunction "VI_3") (pintype "input"))
      (node (ref "IC5") (pin "3") (pinfunction "IN_3") (pintype "input"))
      (node (ref "POWER") (pin "6") (pinfunction "6_6") (pintype "passive"))
      (node (ref "R10") (pin "2") (pinfunction "2_2") (pintype "passive"))
    )
    (net (code "110") (name "/X0") (class "Default")
      (node (ref "CX0") (pin "2") (pinfunction "2_2") (pintype "passive"))
      (node (ref "MCU") (pin "7") (pinfunction "PB6(XTAL1/TOSC1)_7") (pintype "bidirectional"))
      (node (ref "XTAL") (pin "2") (pinfunction "2_2") (pintype "passive"))
    )
    (net (code "111") (name "/X1") (class "Default")
      (node (ref "CX1") (pin "2") (pinfunction "2_2") (pintype "passive"))
      (node (ref "MCU") (pin "8") (pinfunction "PB7(XTAL2/TOSC2)_8") (pintype "bidirectional"))
      (node (ref "XTAL") (pin "1") (pinfunction "1_1") (pintype "passive"))
    )
    (net (code "112") (name "GND") (class "Default")
      (node (ref "ADECOUP") (pin "2") (pinfunction "2_2") (pintype "passive"))
      (node (ref "C1") (pin "2") (pinfunction "2_2") (pintype "passive"))
      (node (ref "C10") (pin "2") (pinfunction "2_2") (pintype "passive"))
      (node (ref "C13") (pin "1") (pinfunction "1_1") (pintype "passive"))
      (node (ref "C17") (pin "1") (pinfunction "1_1") (pintype "passive"))
      (node (ref "C2") (pin "1") (pinfunction "1_1") (pintype "passive"))
      (node (ref "C3") (pin "1") (pinfunction "1_1") (pintype "passive"))
      (node (ref "C4") (pin "2") (pinfunction "2_2") (pintype "passive"))
      (node (ref "C5") (pin "2") (pinfunction "2_2") (pintype "passive"))
      (node (ref "C6") (pin "-") (pinfunction "-_-") (pintype "passive"))
      (node (ref "C7") (pin "-") (pinfunction "-_-") (pintype "passive"))
      (node (ref "C9") (pin "2") (pinfunction "2_2") (pintype "passive"))
      (node (ref "CLOCK_BATT") (pin "GND") (pinfunction "-_GND") (pintype "power_in"))
      (node (ref "COUT") (pin "2") (pinfunction "2_2") (pintype "passive"))
      (node (ref "CX0") (pin "1") (pinfunction "1_1") (pintype "passive"))
      (node (ref "CX1") (pin "1") (pinfunction "1_1") (pintype "passive"))
      (node (ref "C_LDO_SD") (pin "1") (pinfunction "1_1") (pintype "passive"))
      (node (ref "C_LDO_SENSE") (pin "1") (pinfunction "1_1") (pintype "passive"))
      (node (ref "DECOUP") (pin "2") (pinfunction "2_2") (pintype "passive"))
      (node (ref "H1") (pin "2") (pinfunction "2_2") (pintype "passive"))
      (node (ref "H1") (pin "4") (pinfunction "4_4") (pintype "passive"))
      (node (ref "H1") (pin "7") (pinfunction "7_7") (pintype "passive"))
      (node (ref "IC1") (pin "2") (pinfunction "GND_2") (pintype "passive"))
      (node (ref "IC1") (pin "3") (pinfunction "CTL_3") (pintype "input"))
      (node (ref "IC2") (pin "11") (pinfunction "GND_11") (pintype "power_in"))
      (node (ref "IC2") (pin "32") (pinfunction "GND1_32") (pintype "power_in"))
      (node (ref "IC2") (pin "62") (pinfunction "GND2_62") (pintype "power_in"))
      (node (ref "IC2") (pin "81") (pinfunction "GND3_81") (pintype "power_in"))
      (node (ref "IC2") (pin "99") (pinfunction "AGND_99") (pintype "power_in"))
      (node (ref "IC4") (pin "1") (pinfunction "ADJ_1") (pintype "input"))
      (node (ref "IC5") (pin "1") (pinfunction "GND/ADJ_1") (pintype "input"))
      (node (ref "IC7") (pin "4") (pinfunction "V-_4") (pintype "power_in"))
      (node (ref "ISP") (pin "6") (pinfunction "GND_6") (pintype "power_in"))
      (node (ref "J1") (pin "GND") (pinfunction "GND_GND") (pintype "bidirectional"))
      (node (ref "J1") (pin "GNDBREAK") (pinfunction "GNDBREAK_GNDBREAK") (pintype "bidirectional"))
      (node (ref "JP5") (pin "GND") (pinfunction "GND_GND") (pintype "bidirectional"))
      (node (ref "L") (pin "P$2") (pinfunction "C_P$2") (pintype "passive"))
      (node (ref "LD0_SD") (pin "2") (pinfunction "GND_2") (pintype "bidirectional"))
      (node (ref "LD0_SENSE") (pin "2") (pinfunction "GND_2") (pintype "bidirectional"))
      (node (ref "LED") (pin "K") (pinfunction "C_K") (pintype "passive"))
      (node (ref "LSHIFT") (pin "11") (pinfunction "I_11") (pintype "input"))
      (node (ref "LSHIFT") (pin "14") (pinfunction "I_14") (pintype "input"))
      (node (ref "LSHIFT") (pin "8") (pinfunction "VSS_8") (pintype "power_in"))
      (node (ref "LSHIFT") (pin "9") (pinfunction "I_9") (pintype "input"))
      (node (ref "MANUAL_LOG") (pin "C1") (pinfunction "COM1_C1") (pintype "bidirectional"))
      (node (ref "MANUAL_LOG") (pin "C2") (pinfunction "COM2_C2") (pintype "bidirectional"))
      (node (ref "MCU") (pin "21") (pinfunction "GND_21") (pintype "bidirectional"))
      (node (ref "MCU") (pin "3") (pinfunction "GND_3") (pintype "bidirectional"))
      (node (ref "MCU") (pin "5") (pinfunction "AGND_5") (pintype "bidirectional"))
      (node (ref "POWER") (pin "4") (pinfunction "4_4") (pintype "passive"))
      (node (ref "POWER") (pin "5") (pinfunction "5_5") (pintype "passive"))
      (node (ref "PWMH") (pin "7") (pinfunction "7_7") (pintype "passive"))
      (node (ref "R6") (pin "1") (pinfunction "1_1") (pintype "passive"))
      (node (ref "RTC") (pin "10") (pinfunction "NC6_10") (pintype "bidirectional"))
      (node (ref "RTC") (pin "11") (pinfunction "NC7_11") (pintype "bidirectional"))
      (node (ref "RTC") (pin "12") (pinfunction "NC8_12") (pintype "bidirectional"))
      (node (ref "RTC") (pin "13") (pinfunction "GND_13") (pintype "bidirectional"))
      (node (ref "RTC") (pin "5") (pinfunction "NC1_5") (pintype "bidirectional"))
      (node (ref "RTC") (pin "6") (pinfunction "NC2_6") (pintype "bidirectional"))
      (node (ref "RTC") (pin "7") (pinfunction "NC3_7") (pintype "bidirectional"))
      (node (ref "RTC") (pin "8") (pinfunction "NC4_8") (pintype "bidirectional"))
      (node (ref "RTC") (pin "9") (pinfunction "NC5_9") (pintype "bidirectional"))
      (node (ref "R_REF_A0") (pin "1") (pinfunction "1_1") (pintype "passive"))
      (node (ref "R_REF_A1") (pin "1") (pinfunction "1_1") (pintype "passive"))
      (node (ref "R_REF_A2") (pin "1") (pinfunction "1_1") (pintype "passive"))
      (node (ref "R_REF_A3") (pin "1") (pinfunction "1_1") (pintype "passive"))
      (node (ref "R_REF_A6") (pin "1") (pinfunction "1_1") (pintype "passive"))
      (node (ref "R_REF_A7") (pin "1") (pinfunction "1_1") (pintype "passive"))
      (node (ref "S1") (pin "1") (pinfunction "S_1") (pintype "passive"))
      (node (ref "S1") (pin "2") (pinfunction "S1_2") (pintype "passive"))
      (node (ref "S2") (pin "1") (pinfunction "1_1") (pintype "passive"))
      (node (ref "S2") (pin "2") (pinfunction "2_2") (pintype "passive"))
      (node (ref "SD") (pin "3") (pinfunction "VSS1_3") (pintype "power_in"))
      (node (ref "SD") (pin "6") (pinfunction "VSS2_6") (pintype "power_in"))
      (node (ref "SD") (pin "GP") (pinfunction "GND_GP") (pintype "power_in"))
      (node (ref "SD") (pin "GP3") (pinfunction "COMMON_SW_GP3") (pintype "passive"))
      (node (ref "U1") (pin "11") (pinfunction "CTS_11") (pintype "bidirectional"))
      (node (ref "U1") (pin "18") (pinfunction "GND2_18") (pintype "power_in"))
      (node (ref "U1") (pin "21") (pinfunction "GND3_21") (pintype "power_in"))
      (node (ref "U1") (pin "25") (pinfunction "AGND_25") (pintype "power_in"))
      (node (ref "U1") (pin "26") (pinfunction "TEST_26") (pintype "input"))
      (node (ref "U1") (pin "7") (pinfunction "GND1_7") (pintype "power_in"))
      (node (ref "USBD0") (pin "2") (pinfunction "2_2") (pintype "passive"))
      (node (ref "USBD1") (pin "C") (pinfunction "-_C") (pintype "passive"))
      (node (ref "X2") (pin "1") (pinfunction "1_1") (pintype "power_in"))
      (node (ref "X2") (pin "3") (pinfunction "3_3") (pintype "power_in"))
    )
    (net (code "113") (name "Net-(IC1-GATE)") (class "Default")
      (node (ref "IC1") (pin "5") (pinfunction "GATE_5") (pintype "output"))
      (node (ref "Q1") (pin "1") (pinfunction "G_1") (pintype "passive"))
    )
    (net (code "114") (name "Net-(IC1-STAT)") (class "Default")
      (node (ref "IC1") (pin "4") (pinfunction "STAT_4") (pintype "open_collector"))
      (node (ref "Q2") (pin "1") (pinfunction "G_1") (pintype "passive"))
      (node (ref "RSTAT") (pin "1") (pinfunction "1_1") (pintype "passive"))
    )
    (net (code "115") (name "Net-(IC2-XTAL1)") (class "Default")
      (node (ref "C2") (pin "2") (pinfunction "2_2") (pintype "passive"))
      (node (ref "IC2") (pin "34") (pinfunction "XTAL1_34") (pintype "input"))
      (node (ref "Q3") (pin "1") (pinfunction "1_1") (pintype "passive"))
    )
    (net (code "116") (name "Net-(IC2-XTAL2)") (class "Default")
      (node (ref "C3") (pin "2") (pinfunction "2_2") (pintype "passive"))
      (node (ref "IC2") (pin "33") (pinfunction "XTAL2_33") (pintype "output"))
      (node (ref "Q3") (pin "2") (pinfunction "2_2") (pintype "passive"))
    )
    (net (code "117") (name "Net-(IC7A-OUT)") (class "Default")
      (node (ref "IC7") (pin "1") (pinfunction "OUT_1") (pintype "output"))
      (node (ref "IC7") (pin "5") (pinfunction "+IN_5") (pintype "input"))
    )
    (net (code "118") (name "Net-(L-A)") (class "Default")
      (node (ref "L") (pin "P$1") (pinfunction "A_P$1") (pintype "passive"))
      (node (ref "R1") (pin "2") (pinfunction "2_2") (pintype "passive"))
    )
    (net (code "119") (name "Net-(LED-PadA)") (class "Default")
      (node (ref "LED") (pin "A") (pinfunction "A_A") (pintype "passive"))
      (node (ref "R_LED") (pin "2") (pinfunction "2_2") (pintype "passive"))
    )
    (net (code "120") (name "Net-(RX-PadA)") (class "Default")
      (node (ref "RX") (pin "A") (pinfunction "A_A") (pintype "passive"))
      (node (ref "R_RXLED") (pin "2") (pinfunction "2_2") (pintype "passive"))
    )
    (net (code "121") (name "Net-(R_TXLED-Pad2)") (class "Default")
      (node (ref "R_TXLED") (pin "2") (pinfunction "2_2") (pintype "passive"))
      (node (ref "TX") (pin "A") (pinfunction "A_A") (pintype "passive"))
    )
    (net (code "122") (name "Net-(U1-RXLED)") (class "Default")
      (node (ref "RX") (pin "C") (pinfunction "C_C") (pintype "passive"))
      (node (ref "U1") (pin "22") (pinfunction "RXLED_22") (pintype "bidirectional"))
    )
    (net (code "123") (name "Net-(U1-TXLED)") (class "Default")
      (node (ref "TX") (pin "C") (pinfunction "C_C") (pintype "passive"))
      (node (ref "U1") (pin "23") (pinfunction "TXLED_23") (pintype "bidirectional"))
    )
    (net (code "124") (name "Net-(U1-USBDM)") (class "Default")
      (node (ref "JP5") (pin "D-") (pinfunction "D-_D-") (pintype "bidirectional"))
      (node (ref "U1") (pin "16") (pinfunction "USBDM_16") (pintype "bidirectional"))
    )
    (net (code "125") (name "Net-(U1-USBDP)") (class "Default")
      (node (ref "JP5") (pin "D+") (pinfunction "D+_D+") (pintype "bidirectional"))
      (node (ref "U1") (pin "15") (pinfunction "USBDP_15") (pintype "bidirectional"))
    )
    (net (code "126") (name "VCC") (class "Default")
      (node (ref "COUT") (pin "1") (pinfunction "1_1") (pintype "passive"))
      (node (ref "DECOUP") (pin "1") (pinfunction "1_1") (pintype "passive"))
      (node (ref "H1") (pin "3") (pinfunction "3_3") (pintype "passive"))
      (node (ref "H1") (pin "8") (pinfunction "8_8") (pintype "passive"))
      (node (ref "IC1") (pin "6") (pinfunction "SEN_6") (pintype "input"))
      (node (ref "ISP") (pin "2") (pinfunction "VCC_2") (pintype "power_in"))
      (node (ref "J1") (pin "PWR") (pinfunction "PWR_PWR") (pintype "bidirectional"))
      (node (ref "LD0_SD") (pin "1") (pinfunction "VIN_1") (pintype "bidirectional"))
      (node (ref "LD0_SENSE") (pin "1") (pinfunction "VIN_1") (pintype "bidirectional"))
      (node (ref "L_LPF") (pin "1") (pinfunction "1_1") (pintype "passive"))
      (node (ref "MCU") (pin "4") (pinfunction "VCC_4") (pintype "bidirectional"))
      (node (ref "MCU") (pin "6") (pinfunction "VCC_6") (pintype "bidirectional"))
      (node (ref "PU1") (pin "2") (pinfunction "2_2") (pintype "passive"))
      (node (ref "PU2") (pin "2") (pinfunction "2_2") (pintype "passive"))
      (node (ref "Q1") (pin "2") (pinfunction "S_2") (pintype "passive"))
      (node (ref "Q2") (pin "2") (pinfunction "S_2") (pintype "passive"))
      (node (ref "RSTAT") (pin "2") (pinfunction "2_2") (pintype "passive"))
      (node (ref "RTC") (pin "2") (pinfunction "VCC_2") (pintype "bidirectional"))
      (node (ref "R_RESET") (pin "2") (pinfunction "2_2") (pintype "passive"))
    )
    (net (code "127") (name "VDD") (class "Default")
      (node (ref "C_LDO_SD") (pin "2") (pinfunction "2_2") (pintype "passive"))
      (node (ref "LD0_SD") (pin "5") (pinfunction "VOUT_5") (pintype "bidirectional"))
      (node (ref "LSHIFT") (pin "1") (pinfunction "VDD_1") (pintype "power_in"))
      (node (ref "SD") (pin "4") (pinfunction "VDD_4") (pintype "power_in"))
    )
    (net (code "128") (name "VUSB") (class "Default")
      (node (ref "JP5") (pin "VBUS") (pinfunction "VBUS_VBUS") (pintype "bidirectional"))
      (node (ref "Q2") (pin "3") (pinfunction "D_3") (pintype "passive"))
      (node (ref "R_RXLED") (pin "1") (pinfunction "1_1") (pintype "passive"))
      (node (ref "R_TXLED") (pin "1") (pinfunction "1_1") (pintype "passive"))
      (node (ref "U1") (pin "20") (pinfunction "VCC_20") (pintype "power_in"))
      (node (ref "U1") (pin "4") (pinfunction "VCCIO_4") (pintype "power_in"))
      (node (ref "USBD0") (pin "1") (pinfunction "1_1") (pintype "passive"))
      (node (ref "USBD1") (pin "A") (pinfunction "+_A") (pintype "passive"))
    )
    (net (code "129") (name "unconnected-(IC2-(CLKO{slash}ICP3{slash}INT7)PE7-Pad9)") (class "Default")
      (node (ref "IC2") (pin "9") (pinfunction "(CLKO/ICP3/INT7)PE7_9") (pintype "bidirectional"))
    )
    (net (code "130") (name "unconnected-(IC2-(ICP1)PD4-Pad47)") (class "Default")
      (node (ref "IC2") (pin "47") (pinfunction "(ICP1)PD4_47") (pintype "bidirectional"))
    )
    (net (code "131") (name "unconnected-(IC2-(T1)PD6-Pad49)") (class "Default")
      (node (ref "IC2") (pin "49") (pinfunction "(T1)PD6_49") (pintype "bidirectional"))
    )
    (net (code "132") (name "unconnected-(IC2-(T3{slash}INT6)PE6-Pad8)") (class "Default")
      (node (ref "IC2") (pin "8") (pinfunction "(T3/INT6)PE6_8") (pintype "bidirectional"))
    )
    (net (code "133") (name "unconnected-(IC2-(TOSC1)PG4-Pad29)") (class "Default")
      (node (ref "IC2") (pin "29") (pinfunction "(TOSC1)PG4_29") (pintype "bidirectional"))
    )
    (net (code "134") (name "unconnected-(IC2-(TOSC2)PG3-Pad28)") (class "Default")
      (node (ref "IC2") (pin "28") (pinfunction "(TOSC2)PG3_28") (pintype "bidirectional"))
    )
    (net (code "135") (name "unconnected-(IC2-(XCK0{slash}AIN0)PE2-Pad4)") (class "Default")
      (node (ref "IC2") (pin "4") (pinfunction "(XCK0/AIN0)PE2_4") (pintype "bidirectional"))
    )
    (net (code "136") (name "unconnected-(IC2-(XCK1)PD5-Pad48)") (class "Default")
      (node (ref "IC2") (pin "48") (pinfunction "(XCK1)PD5_48") (pintype "bidirectional"))
    )
    (net (code "137") (name "unconnected-(IC2-PH2(XCK2)-Pad14)") (class "Default")
      (node (ref "IC2") (pin "14") (pinfunction "PH2(XCK2)_14") (pintype "bidirectional"))
    )
    (net (code "138") (name "unconnected-(IC2-PH7(T4)-Pad27)") (class "Default")
      (node (ref "IC2") (pin "27") (pinfunction "PH7(T4)_27") (pintype "bidirectional"))
    )
    (net (code "139") (name "unconnected-(IC2-PJ2(XCK3{slash}PCINT11)-Pad65)") (class "Default")
      (node (ref "IC2") (pin "65") (pinfunction "PJ2(XCK3/PCINT11)_65") (pintype "bidirectional"))
    )
    (net (code "140") (name "unconnected-(IC2-PJ3(PCINT12)-Pad66)") (class "Default")
      (node (ref "IC2") (pin "66") (pinfunction "PJ3(PCINT12)_66") (pintype "bidirectional"))
    )
    (net (code "141") (name "unconnected-(IC2-PJ4(PCINT13)-Pad67)") (class "Default")
      (node (ref "IC2") (pin "67") (pinfunction "PJ4(PCINT13)_67") (pintype "bidirectional"))
    )
    (net (code "142") (name "unconnected-(IC2-PJ5(PCINT14)-Pad68)") (class "Default")
      (node (ref "IC2") (pin "68") (pinfunction "PJ5(PCINT14)_68") (pintype "bidirectional"))
    )
    (net (code "143") (name "unconnected-(IC2-PJ6(PCINT15)-Pad69)") (class "Default")
      (node (ref "IC2") (pin "69") (pinfunction "PJ6(PCINT15)_69") (pintype "bidirectional"))
    )
    (net (code "144") (name "unconnected-(IC2-PJ7-Pad79)") (class "Default")
      (node (ref "IC2") (pin "79") (pinfunction "PJ7_79") (pintype "bidirectional"))
    )
    (net (code "145") (name "unconnected-(LD0_SD-BYP-Pad4)") (class "Default")
      (node (ref "LD0_SD") (pin "4") (pinfunction "BYP_4") (pintype "bidirectional"))
    )
    (net (code "146") (name "unconnected-(LD0_SENSE-BYP-Pad4)") (class "Default")
      (node (ref "LD0_SENSE") (pin "4") (pinfunction "BYP_4") (pintype "bidirectional"))
    )
    (net (code "147") (name "unconnected-(LSHIFTD-O-Pad10)") (class "Default")
      (node (ref "LSHIFT") (pin "10") (pinfunction "O_10") (pintype "output"))
    )
    (net (code "148") (name "unconnected-(LSHIFTE-O-Pad12)") (class "Default")
      (node (ref "LSHIFT") (pin "12") (pinfunction "O_12") (pintype "output"))
    )
    (net (code "149") (name "unconnected-(LSHIFTF-O-Pad15)") (class "Default")
      (node (ref "LSHIFT") (pin "15") (pinfunction "O_15") (pintype "output"))
    )
    (net (code "150") (name "unconnected-(RTC-32KHZ-Pad1)") (class "Default")
      (node (ref "RTC") (pin "1") (pinfunction "32KHZ_1") (pintype "bidirectional"))
    )
    (net (code "151") (name "unconnected-(RTC-~{RST}-Pad4)") (class "Default")
      (node (ref "RTC") (pin "4") (pinfunction "~{RST}_4") (pintype "bidirectional"))
    )
    (net (code "152") (name "unconnected-(SD-DAT1-Pad8)") (class "Default")
      (node (ref "SD") (pin "8") (pinfunction "DAT1_8") (pintype "bidirectional"))
    )
    (net (code "153") (name "unconnected-(SD-DAT2-Pad9)") (class "Default")
      (node (ref "SD") (pin "9") (pinfunction "DAT2_9") (pintype "bidirectional"))
    )
    (net (code "154") (name "unconnected-(SD-WRITE_PROTECT-PadWP)") (class "Default")
      (node (ref "SD") (pin "WP") (pinfunction "WRITE_PROTECT_WP") (pintype "passive"))
    )
    (net (code "155") (name "unconnected-(T1-D2-Pad4)") (class "Default")
      (node (ref "T1") (pin "4") (pinfunction "D2_4") (pintype "passive"))
    )
    (net (code "156") (name "unconnected-(U1-3V3OUT-Pad17)") (class "Default")
      (node (ref "U1") (pin "17") (pinfunction "3V3OUT_17") (pintype "output"))
    )
    (net (code "157") (name "unconnected-(U1-RTS-Pad3)") (class "Default")
      (node (ref "U1") (pin "3") (pinfunction "RTS_3") (pintype "bidirectional"))
    )
  )
)
